# IoT_BOS_frigo.net
KiCad netlist of a schematic drawn in EasyEDA
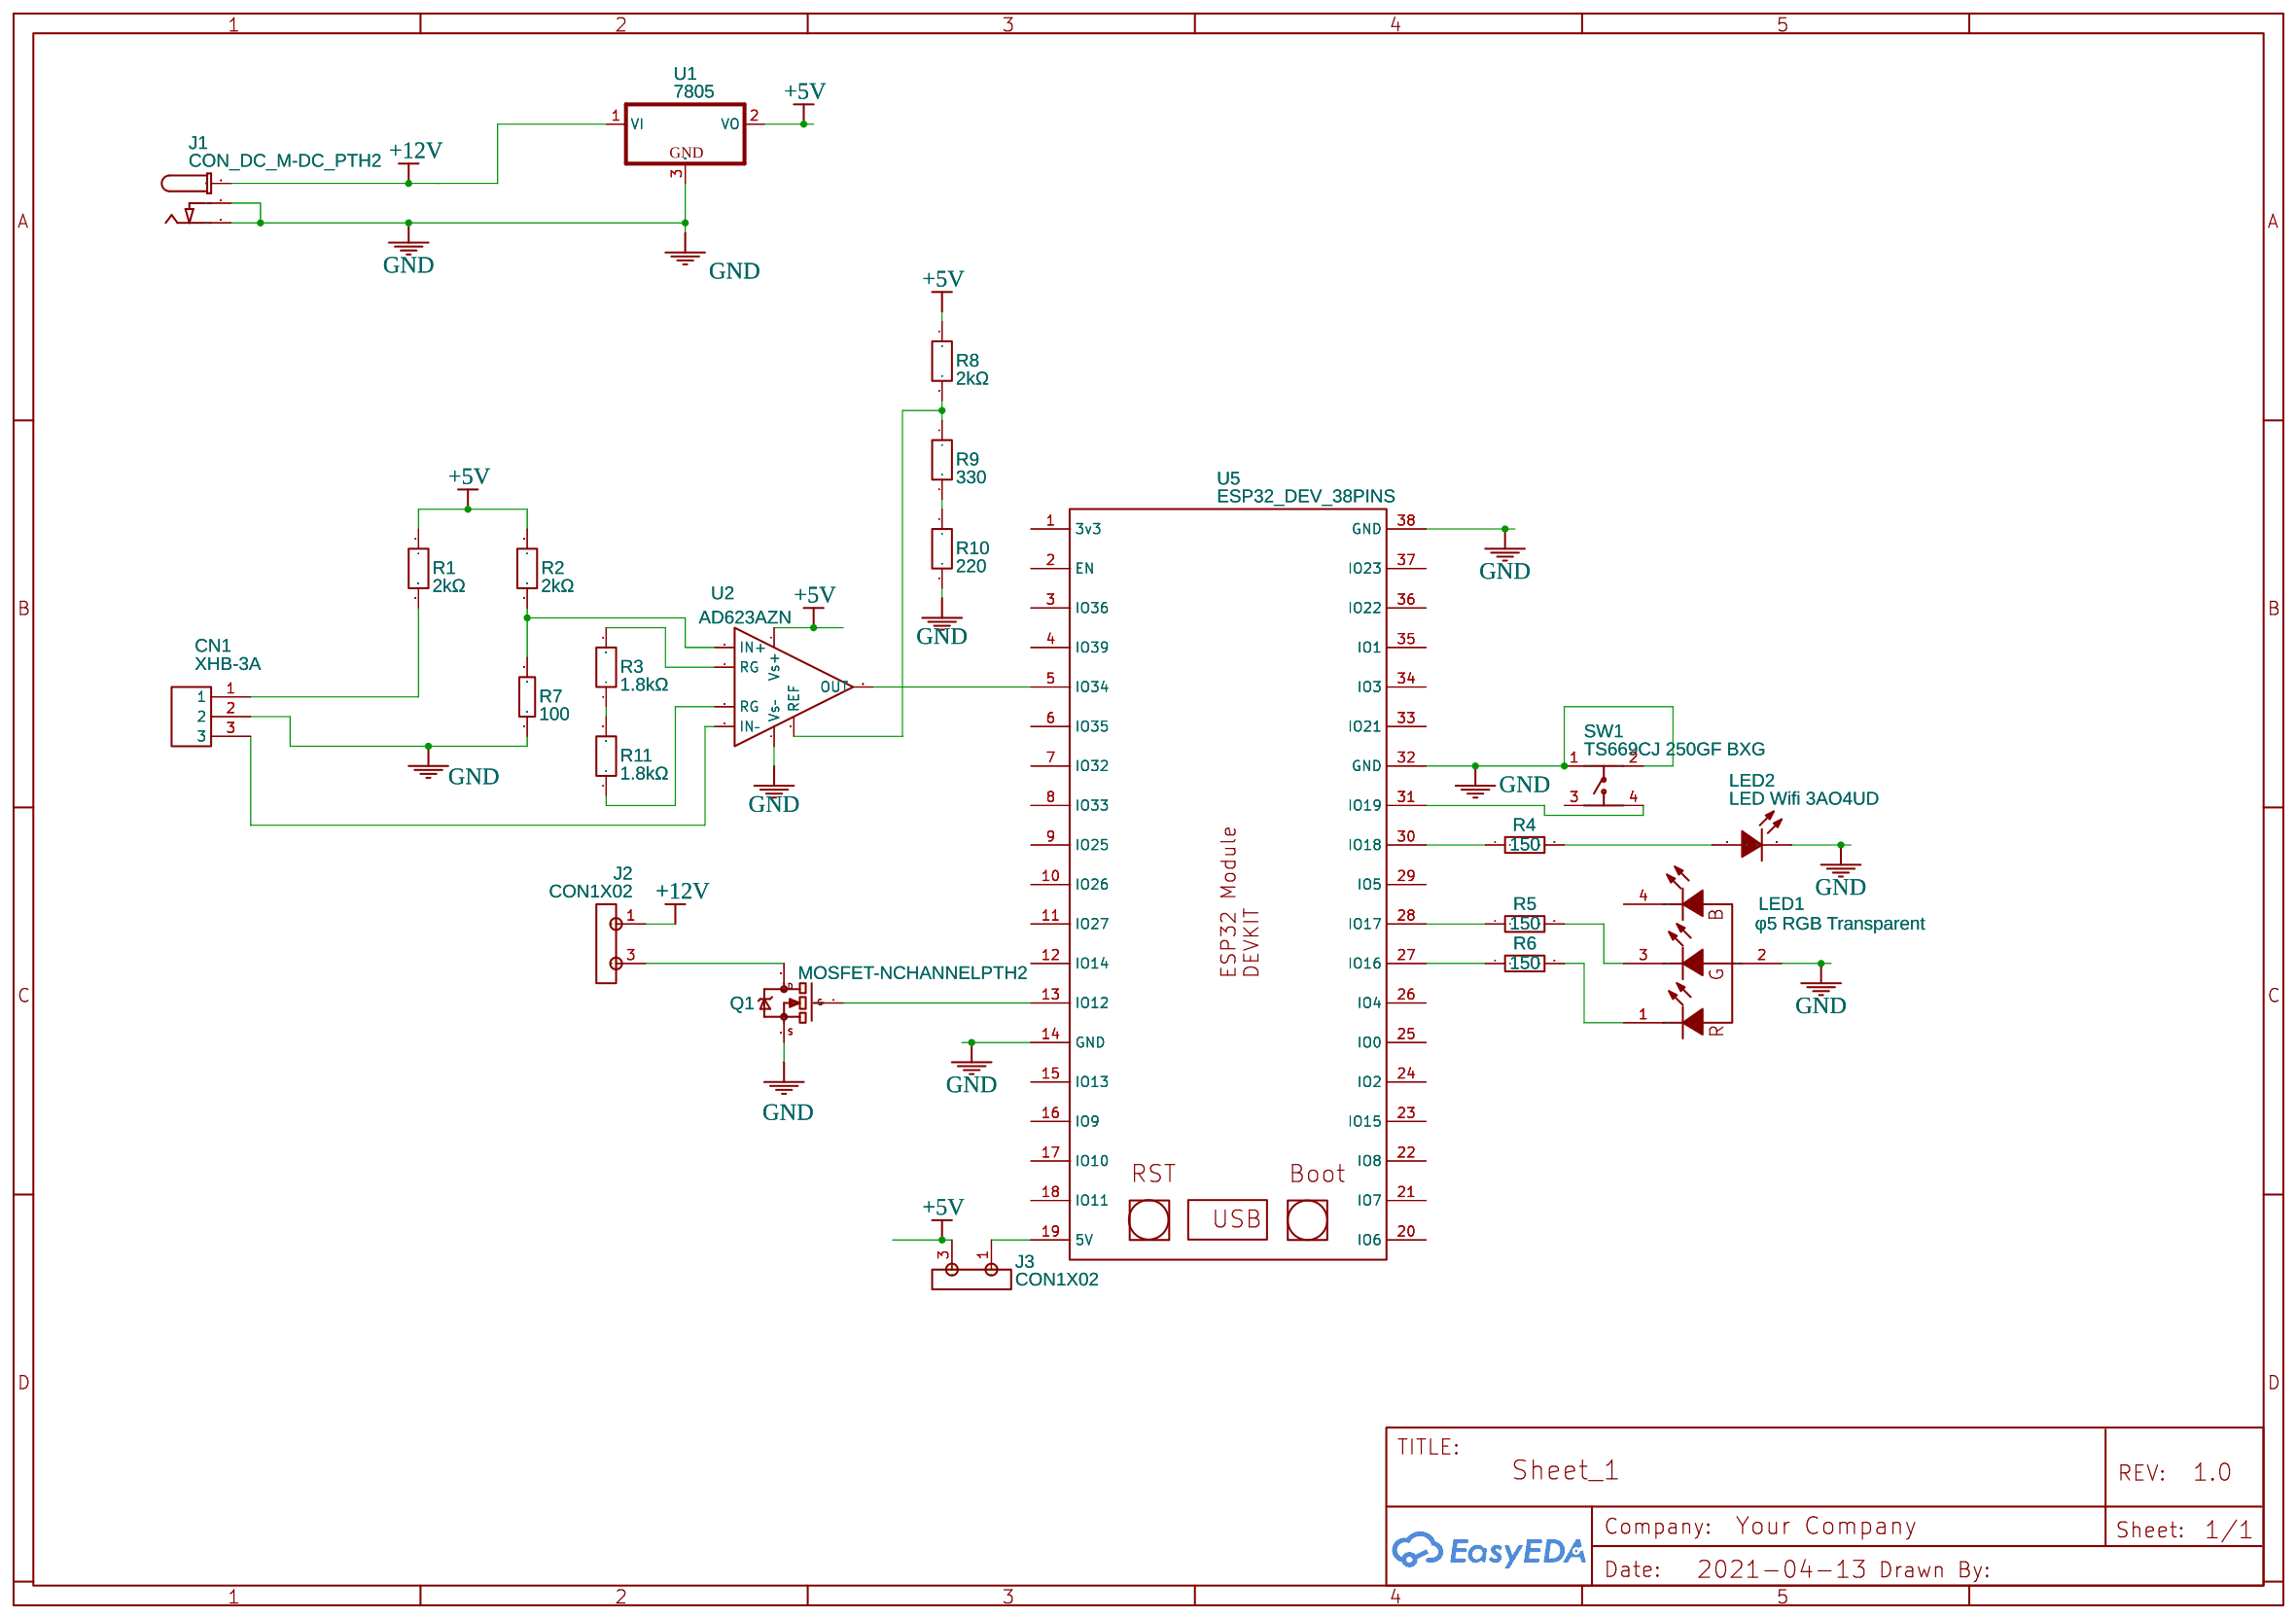
[diagram p0: schematic sheet]

(export (version "E")
  (design (tool "Eeschema 10.0.6"))
  (components
    (comp (ref "CN1")
      (value "XHB-3A")
      (fields (field (name "BOM_Supplier Part") "C68817"))
      (libsource (lib "") (part "XHB-3A"))
    )
    (comp (ref "J1") (value "CON_DC_M-DC_PTH2") (libsource (lib "") (part "CON_DC_M-DC_PTH2")))
    (comp (ref "J2") (value "CON1X02") (libsource (lib "") (part "CON1X02")))
    (comp (ref "J3") (value "CON1X02") (libsource (lib "") (part "CON1X02_1")))
    (comp (ref "LED1")
      (value "φ5 RGB Transparent")
      (fields
        (field (name "BOM_Manufacturer Part") "φ5 RGB Transparent LED")
        (field (name "BOM_Supplier Part") "C32985")
      )
      (libsource (lib "") (part "φ5 RGB Transparent"))
    )
    (comp (ref "LED2")
      (value "LED Wifi 3AO4UD")
      (fields
        (field (name "BOM_Manufacturer Part") "LEDOrange orange 3AO4UD")
        (field (name "BOM_Supplier Part") "C62095")
      )
      (libsource (lib "") (part "LEDOrange orange 3AO4UD"))
    )
    (comp (ref "Q1") (value "MOSFET-NCHANNELPTH2") (libsource (lib "") (part "MOSFET-NCHANNELPTH2")))
    (comp (ref "R1")
      (value "2kΩ")
      (fields
        (field (name "BOM_Manufacturer Part") "CF1/4W-2KΩ±5%T52")
        (field (name "BOM_Supplier Part") "C714305")
      )
      (libsource (lib "") (part "CF1/4W-2KΩ±5%T52"))
    )
    (comp (ref "R2")
      (value "2kΩ")
      (fields
        (field (name "BOM_Manufacturer Part") "CF1/4W-2KΩ±5%T52")
        (field (name "BOM_Supplier Part") "C714305")
      )
      (libsource (lib "") (part "CF1/4W-2KΩ±5%T52"))
    )
    (comp (ref "R3")
      (value "1.8kΩ")
      (fields
        (field (name "BOM_Manufacturer Part") "CF1/4W-1.8KΩ±5%T52")
        (field (name "BOM_Supplier Part") "C714304")
      )
      (libsource (lib "") (part "CF1/4W-1.8KΩ±5%T52"))
    )
    (comp (ref "R4")
      (value "150")
      (fields
        (field (name "BOM_Manufacturer Part") "CFR03SJ0151AA0")
        (field (name "BOM_Supplier Part") "C69877")
      )
      (libsource (lib "") (part "CFR03SJ0151AA0"))
    )
    (comp (ref "R5")
      (value "150")
      (fields
        (field (name "BOM_Manufacturer Part") "CFR03SJ0151AA0")
        (field (name "BOM_Supplier Part") "C69877")
      )
      (libsource (lib "") (part "CFR03SJ0151AA0"))
    )
    (comp (ref "R6")
      (value "150")
      (fields
        (field (name "BOM_Manufacturer Part") "CFR03SJ0151AA0")
        (field (name "BOM_Supplier Part") "C69877")
      )
      (libsource (lib "") (part "CFR03SJ0151AA0"))
    )
    (comp (ref "R7")
      (value "100")
      (fields
        (field (name "BOM_Manufacturer Part") "CFR0S2J0101A10")
        (field (name "BOM_Supplier Part") "C61282")
      )
      (libsource (lib "") (part "CFR0S2J0101A10"))
    )
    (comp (ref "R8")
      (value "2kΩ")
      (fields
        (field (name "BOM_Manufacturer Part") "CF1/4W-2KΩ±5%T52")
        (field (name "BOM_Supplier Part") "C714305")
      )
      (libsource (lib "") (part "CF1/4W-2KΩ±5%T52"))
    )
    (comp (ref "R9")
      (value "330")
      (fields
        (field (name "BOM_Manufacturer Part") "CF1/4W-2KΩ±5%T52")
        (field (name "BOM_Supplier Part") "C714305")
      )
      (libsource (lib "") (part "CF1/4W-2KΩ±5%T52"))
    )
    (comp (ref "R10")
      (value "220")
      (fields
        (field (name "BOM_Manufacturer Part") "CF1/4W-2KΩ±5%T52")
        (field (name "BOM_Supplier Part") "C714305")
      )
      (libsource (lib "") (part "CF1/4W-2KΩ±5%T52"))
    )
    (comp (ref "R11")
      (value "1.8kΩ")
      (fields
        (field (name "BOM_Manufacturer Part") "CF1/4W-1.8KΩ±5%T52")
        (field (name "BOM_Supplier Part") "C714304")
      )
      (libsource (lib "") (part "CF1/4W-1.8KΩ±5%T52"))
    )
    (comp (ref "SW1")
      (value "TS669CJ 250GF BXG")
      (fields
        (field (name "BOM_Manufacturer Part") "TS669CJ 250gf BXG")
        (field (name "BOM_Supplier Part") "C2765193")
      )
      (libsource (lib "") (part "TS669CJ 250GF BXG"))
    )
    (comp (ref "U1") (value "7805") (libsource (lib "") (part "7805")))
    (comp (ref "U2") (value "AD623AZN") (libsource (lib "") (part "AD620N")))
    (comp (ref "U5")
      (value "ESP32_DEV_38PINS")
      (fields (field (name "BOM_Manufacturer Part") "ESP32 DEV KIT"))
      (libsource (lib "") (part "ESP32_DEV_38PINS"))
    )
  )
  (nets
    (net (code "1") (name "+5V") (class "Default")
      (node (ref "J3") (pin "3") (pinfunction "2_3") (pintype "unspecified"))
      (node (ref "R1") (pin "1") (pinfunction "1_1") (pintype "unspecified"))
      (node (ref "R2") (pin "1") (pinfunction "1_1") (pintype "unspecified"))
      (node (ref "R8") (pin "1") (pinfunction "1_1") (pintype "unspecified"))
      (node (ref "U1") (pin "2") (pinfunction "VO_2") (pintype "unspecified"))
      (node (ref "U2") (pin "7") (pinfunction "Vs+_7") (pintype "unspecified"))
    )
    (net (code "2") (name "+12V") (class "Default")
      (node (ref "J1") (pin "P1") (pinfunction "P1_P1") (pintype "unspecified"))
      (node (ref "J2") (pin "1") (pinfunction "1_1") (pintype "unspecified"))
      (node (ref "U1") (pin "1") (pinfunction "VI_1") (pintype "input"))
    )
    (net (code "3") (name "GND") (class "Default")
      (node (ref "CN1") (pin "2") (pinfunction "2_2") (pintype "unspecified"))
      (node (ref "J1") (pin "P2") (pinfunction "P3_P2") (pintype "unspecified"))
      (node (ref "J1") (pin "P3") (pinfunction "P2_P3") (pintype "unspecified"))
      (node (ref "LED1") (pin "2") (pinfunction "CA_2") (pintype "unspecified"))
      (node (ref "LED2") (pin "2") (pinfunction "K_2") (pintype "unspecified"))
      (node (ref "Q1") (pin "2") (pinfunction "S_2") (pintype "unspecified"))
      (node (ref "R10") (pin "2") (pinfunction "2_2") (pintype "unspecified"))
      (node (ref "R7") (pin "1") (pinfunction "1_1") (pintype "input"))
      (node (ref "SW1") (pin "1") (pinfunction "1_1") (pintype "unspecified"))
      (node (ref "SW1") (pin "2") (pinfunction "2_2") (pintype "unspecified"))
      (node (ref "U1") (pin "3") (pinfunction "GND_3") (pintype "unspecified"))
      (node (ref "U2") (pin "4") (pinfunction "Vs–_4") (pintype "unspecified"))
      (node (ref "U5") (pin "14") (pinfunction "GND_14") (pintype "bidirectional"))
      (node (ref "U5") (pin "32") (pinfunction "GND_32") (pintype "passive"))
      (node (ref "U5") (pin "38") (pinfunction "GND_38") (pintype "passive"))
    )
    (net (code "4") (name "Net-(CN1-Pad1)") (class "Default")
      (node (ref "CN1") (pin "1") (pinfunction "1_1") (pintype "unspecified"))
      (node (ref "R1") (pin "2") (pinfunction "2_2") (pintype "unspecified"))
    )
    (net (code "5") (name "Net-(J2-2)") (class "Default")
      (node (ref "J2") (pin "3") (pinfunction "2_3") (pintype "unspecified"))
      (node (ref "Q1") (pin "3") (pinfunction "D_3") (pintype "unspecified"))
    )
    (net (code "6") (name "Net-(LED1-KG)") (class "Default")
      (node (ref "LED1") (pin "3") (pinfunction "KG_3") (pintype "unspecified"))
      (node (ref "R5") (pin "2") (pinfunction "2_2") (pintype "input"))
    )
    (net (code "7") (name "Net-(LED1-KR)") (class "Default")
      (node (ref "LED1") (pin "1") (pinfunction "KR_1") (pintype "unspecified"))
      (node (ref "R6") (pin "2") (pinfunction "2_2") (pintype "input"))
    )
    (net (code "8") (name "Net-(LED2-A)") (class "Default")
      (node (ref "LED2") (pin "1") (pinfunction "A_1") (pintype "unspecified"))
      (node (ref "R4") (pin "2") (pinfunction "2_2") (pintype "input"))
    )
    (net (code "9") (name "Net-(Q1-G)") (class "Default")
      (node (ref "Q1") (pin "1") (pinfunction "G_1") (pintype "unspecified"))
      (node (ref "U5") (pin "13") (pinfunction "IO12_13") (pintype "bidirectional"))
    )
    (net (code "10") (name "Net-(R3-Pad2)") (class "Default")
      (node (ref "R3") (pin "2") (pinfunction "2_2") (pintype "unspecified"))
      (node (ref "U2") (pin "1") (pinfunction "RG_1") (pintype "unspecified"))
    )
    (net (code "11") (name "Net-(R10-Pad1)") (class "Default")
      (node (ref "R10") (pin "1") (pinfunction "1_1") (pintype "unspecified"))
      (node (ref "R9") (pin "2") (pinfunction "2_2") (pintype "unspecified"))
    )
    (net (code "12") (name "Net-(R11-Pad1)") (class "Default")
      (node (ref "R11") (pin "1") (pinfunction "1_1") (pintype "unspecified"))
      (node (ref "U2") (pin "8") (pinfunction "RG_8") (pintype "unspecified"))
    )
    (net (code "13") (name "Net-(R11-Pad2)") (class "Default")
      (node (ref "R11") (pin "2") (pinfunction "2_2") (pintype "unspecified"))
      (node (ref "R3") (pin "1") (pinfunction "1_1") (pintype "unspecified"))
    )
    (net (code "14") (name "Net-(U2-IN+)") (class "Default")
      (node (ref "R2") (pin "2") (pinfunction "2_2") (pintype "unspecified"))
      (node (ref "R7") (pin "2") (pinfunction "2_2") (pintype "input"))
      (node (ref "U2") (pin "3") (pinfunction "IN+_3") (pintype "unspecified"))
    )
    (net (code "15") (name "Net-(U2-IN–)") (class "Default")
      (node (ref "CN1") (pin "3") (pinfunction "3_3") (pintype "unspecified"))
      (node (ref "U2") (pin "2") (pinfunction "IN–_2") (pintype "unspecified"))
    )
    (net (code "16") (name "Net-(U2-OUT)") (class "Default")
      (node (ref "U2") (pin "6") (pinfunction "OUT_6") (pintype "unspecified"))
      (node (ref "U5") (pin "5") (pinfunction "IO34_5") (pintype "bidirectional"))
    )
    (net (code "17") (name "Net-(U2-REF)") (class "Default")
      (node (ref "R8") (pin "2") (pinfunction "2_2") (pintype "unspecified"))
      (node (ref "R9") (pin "1") (pinfunction "1_1") (pintype "unspecified"))
      (node (ref "U2") (pin "5") (pinfunction "REF_5") (pintype "unspecified"))
    )
    (net (code "18") (name "Net-(U5-5V)") (class "Default")
      (node (ref "J3") (pin "1") (pinfunction "1_1") (pintype "unspecified"))
      (node (ref "U5") (pin "19") (pinfunction "5V_19") (pintype "unspecified"))
    )
    (net (code "19") (name "Net-(U5-IO16)") (class "Default")
      (node (ref "R6") (pin "1") (pinfunction "1_1") (pintype "input"))
      (node (ref "U5") (pin "27") (pinfunction "IO16_27") (pintype "unspecified"))
    )
    (net (code "20") (name "Net-(U5-IO17)") (class "Default")
      (node (ref "R5") (pin "1") (pinfunction "1_1") (pintype "input"))
      (node (ref "U5") (pin "28") (pinfunction "IO17_28") (pintype "bidirectional"))
    )
    (net (code "21") (name "Net-(U5-IO18)") (class "Default")
      (node (ref "R4") (pin "1") (pinfunction "1_1") (pintype "input"))
      (node (ref "U5") (pin "30") (pinfunction "IO18_30") (pintype "passive"))
    )
    (net (code "22") (name "Net-(U5-IO19)") (class "Default")
      (node (ref "SW1") (pin "4") (pinfunction "4_4") (pintype "unspecified"))
      (node (ref "U5") (pin "31") (pinfunction "IO19_31") (pintype "passive"))
    )
    (net (code "23") (name "unconnected-(LED1-KB-Pad4)") (class "Default")
      (node (ref "LED1") (pin "4") (pinfunction "KB_4") (pintype "unspecified"))
    )
    (net (code "24") (name "unconnected-(SW1-Pad3)") (class "Default")
      (node (ref "SW1") (pin "3") (pinfunction "3_3") (pintype "unspecified"))
    )
    (net (code "25") (name "unconnected-(U5-3v3-Pad1)") (class "Default")
      (node (ref "U5") (pin "1") (pinfunction "3v3_1") (pintype "passive"))
    )
    (net (code "26") (name "unconnected-(U5-EN-Pad2)") (class "Default")
      (node (ref "U5") (pin "2") (pinfunction "EN_2") (pintype "passive"))
    )
    (net (code "27") (name "unconnected-(U5-IO0-Pad25)") (class "Default")
      (node (ref "U5") (pin "25") (pinfunction "IO0_25") (pintype "unspecified"))
    )
    (net (code "28") (name "unconnected-(U5-IO1-Pad35)") (class "Default")
      (node (ref "U5") (pin "35") (pinfunction "IO1_35") (pintype "passive"))
    )
    (net (code "29") (name "unconnected-(U5-IO2-Pad24)") (class "Default")
      (node (ref "U5") (pin "24") (pinfunction "IO2_24") (pintype "unspecified"))
    )
    (net (code "30") (name "unconnected-(U5-IO3-Pad34)") (class "Default")
      (node (ref "U5") (pin "34") (pinfunction "IO3_34") (pintype "passive"))
    )
    (net (code "31") (name "unconnected-(U5-IO4-Pad26)") (class "Default")
      (node (ref "U5") (pin "26") (pinfunction "IO4_26") (pintype "unspecified"))
    )
    (net (code "32") (name "unconnected-(U5-IO5-Pad29)") (class "Default")
      (node (ref "U5") (pin "29") (pinfunction "IO5_29") (pintype "passive"))
    )
    (net (code "33") (name "unconnected-(U5-IO6-Pad20)") (class "Default")
      (node (ref "U5") (pin "20") (pinfunction "IO6_20") (pintype "unspecified"))
    )
    (net (code "34") (name "unconnected-(U5-IO7-Pad21)") (class "Default")
      (node (ref "U5") (pin "21") (pinfunction "IO7_21") (pintype "unspecified"))
    )
    (net (code "35") (name "unconnected-(U5-IO8-Pad22)") (class "Default")
      (node (ref "U5") (pin "22") (pinfunction "IO8_22") (pintype "unspecified"))
    )
    (net (code "36") (name "unconnected-(U5-IO9-Pad16)") (class "Default")
      (node (ref "U5") (pin "16") (pinfunction "IO9_16") (pintype "unspecified"))
    )
    (net (code "37") (name "unconnected-(U5-IO10-Pad17)") (class "Default")
      (node (ref "U5") (pin "17") (pinfunction "IO10_17") (pintype "unspecified"))
    )
    (net (code "38") (name "unconnected-(U5-IO11-Pad18)") (class "Default")
      (node (ref "U5") (pin "18") (pinfunction "IO11_18") (pintype "unspecified"))
    )
    (net (code "39") (name "unconnected-(U5-IO13-Pad15)") (class "Default")
      (node (ref "U5") (pin "15") (pinfunction "IO13_15") (pintype "bidirectional"))
    )
    (net (code "40") (name "unconnected-(U5-IO14-Pad12)") (class "Default")
      (node (ref "U5") (pin "12") (pinfunction "IO14_12") (pintype "bidirectional"))
    )
    (net (code "41") (name "unconnected-(U5-IO15-Pad23)") (class "Default")
      (node (ref "U5") (pin "23") (pinfunction "IO15_23") (pintype "unspecified"))
    )
    (net (code "42") (name "unconnected-(U5-IO21-Pad33)") (class "Default")
      (node (ref "U5") (pin "33") (pinfunction "IO21_33") (pintype "passive"))
    )
    (net (code "43") (name "unconnected-(U5-IO22-Pad36)") (class "Default")
      (node (ref "U5") (pin "36") (pinfunction "IO22_36") (pintype "passive"))
    )
    (net (code "44") (name "unconnected-(U5-IO23-Pad37)") (class "Default")
      (node (ref "U5") (pin "37") (pinfunction "IO23_37") (pintype "passive"))
    )
    (net (code "45") (name "unconnected-(U5-IO25-Pad9)") (class "Default")
      (node (ref "U5") (pin "9") (pinfunction "IO25_9") (pintype "unspecified"))
    )
    (net (code "46") (name "unconnected-(U5-IO26-Pad10)") (class "Default")
      (node (ref "U5") (pin "10") (pinfunction "IO26_10") (pintype "bidirectional"))
    )
    (net (code "47") (name "unconnected-(U5-IO27-Pad11)") (class "Default")
      (node (ref "U5") (pin "11") (pinfunction "IO27_11") (pintype "bidirectional"))
    )
    (net (code "48") (name "unconnected-(U5-IO32-Pad7)") (class "Default")
      (node (ref "U5") (pin "7") (pinfunction "IO32_7") (pintype "bidirectional"))
    )
    (net (code "49") (name "unconnected-(U5-IO33-Pad8)") (class "Default")
      (node (ref "U5") (pin "8") (pinfunction "IO33_8") (pintype "unspecified"))
    )
    (net (code "50") (name "unconnected-(U5-IO35-Pad6)") (class "Default")
      (node (ref "U5") (pin "6") (pinfunction "IO35_6") (pintype "bidirectional"))
    )
    (net (code "51") (name "unconnected-(U5-IO36-Pad3)") (class "Default")
      (node (ref "U5") (pin "3") (pinfunction "IO36_3") (pintype "bidirectional"))
    )
    (net (code "52") (name "unconnected-(U5-IO39-Pad4)") (class "Default")
      (node (ref "U5") (pin "4") (pinfunction "IO39_4") (pintype "bidirectional"))
    )
  )
)
